# OnOnfre_plug_dev_nao_usar.net
KiCad netlist of a schematic drawn in EAGLE
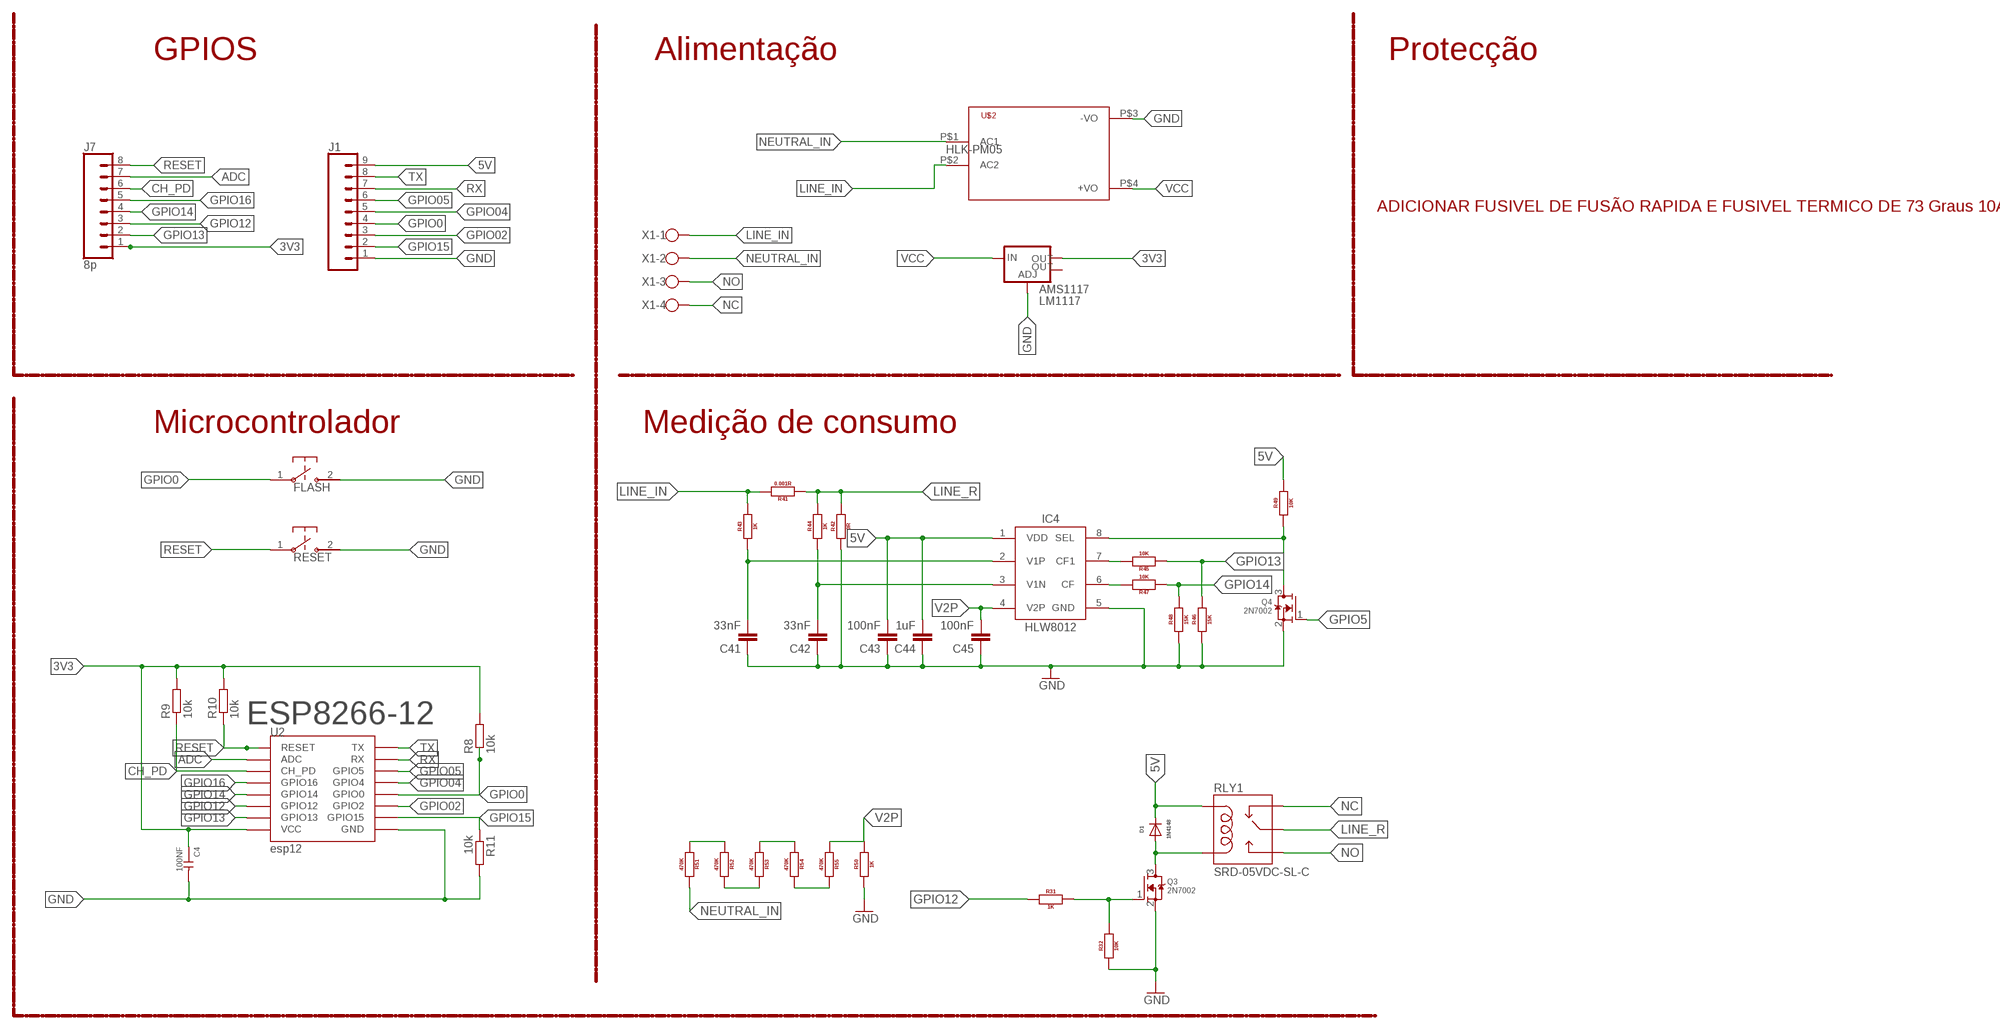
[diagram p0: schematic, sheet 1]

(export (version "E")
  (design (tool "Eeschema 10.0.6"))
  (components
    (comp (ref "AMS1117")
      (value "LM1117")
      (footprint "eagle-import:SOT223")
      (libsource (lib "eagle-import") (part "V_REG_LM1117SOT223"))
    )
    (comp (ref "C4")
      (value "100NF")
      (footprint "eagle-import:C1206")
      (fields (field (name "MPN") "CC1206KKX7RCBB102"))
      (libsource (lib "eagle-import") (part "CERAMIC-1NF-1KV-10%-X7R?(1206)"))
    )
    (comp (ref "C41")
      (value "33nF")
      (footprint "eagle-import:0805")
      (libsource (lib "eagle-import") (part "C-EU0805"))
    )
    (comp (ref "C42")
      (value "33nF")
      (footprint "eagle-import:0805")
      (libsource (lib "eagle-import") (part "C-EU0805"))
    )
    (comp (ref "C43")
      (value "100nF")
      (footprint "eagle-import:0805")
      (libsource (lib "eagle-import") (part "C-EU0805"))
    )
    (comp (ref "C44")
      (value "1uF")
      (footprint "eagle-import:0805")
      (libsource (lib "eagle-import") (part "C-EU0805"))
    )
    (comp (ref "C45")
      (value "100nF")
      (footprint "eagle-import:0805")
      (libsource (lib "eagle-import") (part "C-EU0805"))
    )
    (comp (ref "D1")
      (value "1N4148")
      (footprint "eagle-import:SOD80")
      (libsource (lib "eagle-import") (part "DIODE"))
    )
    (comp (ref "FLASH")
      (value "B3U-1000P-2P-SMD")
      (footprint "eagle-import:B3U-1000P")
      (fields (field (name "MANUFACTURER") "Omron") (field (name "MPN") "B3U-1000P"))
      (libsource (lib "eagle-import") (part "B3U-1000P"))
    )
    (comp (ref "IC4")
      (value "HLW8012")
      (footprint "eagle-import:SOP8")
      (libsource (lib "eagle-import") (part "HLW8012"))
    )
    (comp (ref "J1")
      (value "CONN_09")
      (footprint "eagle-import:1X09")
      (libsource (lib "eagle-import") (part "CONN_09"))
    )
    (comp (ref "J7")
      (value "8p")
      (footprint "eagle-import:1X08")
      (libsource (lib "eagle-import") (part "CONN_08{dblquote}"))
    )
    (comp (ref "Q3")
      (value "2N7002")
      (footprint "eagle-import:SOT23")
      (libsource (lib "eagle-import") (part "MOSFET-NREFLOW"))
    )
    (comp (ref "Q4")
      (value "2N7002")
      (footprint "eagle-import:SOT23")
      (libsource (lib "eagle-import") (part "MOSFET-NREFLOW"))
    )
    (comp (ref "R8")
      (value "10k")
      (footprint "eagle-import:R0603")
      (libsource (lib "eagle-import") (part "R-EU_R0603"))
    )
    (comp (ref "R9")
      (value "10k")
      (footprint "eagle-import:R0603")
      (libsource (lib "eagle-import") (part "R-EU_R0603"))
    )
    (comp (ref "R10")
      (value "10k")
      (footprint "eagle-import:R0603")
      (libsource (lib "eagle-import") (part "R-EU_R0603"))
    )
    (comp (ref "R11")
      (value "10k")
      (footprint "eagle-import:R0603")
      (libsource (lib "eagle-import") (part "R-EU_R0603"))
    )
    (comp (ref "R31")
      (value "1K")
      (footprint "eagle-import:0805")
      (libsource (lib "eagle-import") (part "RESISTOR0805"))
    )
    (comp (ref "R32")
      (value "10K")
      (footprint "eagle-import:0805")
      (libsource (lib "eagle-import") (part "RESISTOR0805"))
    )
    (comp (ref "R41")
      (value "0.001R")
      (footprint "eagle-import:2512")
      (libsource (lib "eagle-import") (part "RESISTOR2512"))
    )
    (comp (ref "R42")
      (value "0R")
      (footprint "eagle-import:1206")
      (libsource (lib "eagle-import") (part "RESISTOR1206"))
    )
    (comp (ref "R43")
      (value "1K")
      (footprint "eagle-import:0805")
      (libsource (lib "eagle-import") (part "RESISTOR0805"))
    )
    (comp (ref "R44")
      (value "1K")
      (footprint "eagle-import:0805")
      (libsource (lib "eagle-import") (part "RESISTOR0805"))
    )
    (comp (ref "R45")
      (value "10K")
      (footprint "eagle-import:0805")
      (libsource (lib "eagle-import") (part "RESISTOR0805"))
    )
    (comp (ref "R46")
      (value "15K")
      (footprint "eagle-import:0805")
      (libsource (lib "eagle-import") (part "RESISTOR0805"))
    )
    (comp (ref "R47")
      (value "10K")
      (footprint "eagle-import:0805")
      (libsource (lib "eagle-import") (part "RESISTOR0805"))
    )
    (comp (ref "R48")
      (value "15K")
      (footprint "eagle-import:0805")
      (libsource (lib "eagle-import") (part "RESISTOR0805"))
    )
    (comp (ref "R49")
      (value "10K")
      (footprint "eagle-import:0805")
      (libsource (lib "eagle-import") (part "RESISTOR0805"))
    )
    (comp (ref "R50")
      (value "1K")
      (footprint "eagle-import:0805")
      (libsource (lib "eagle-import") (part "RESISTOR0805"))
    )
    (comp (ref "R51")
      (value "470K")
      (footprint "eagle-import:0805")
      (libsource (lib "eagle-import") (part "RESISTOR0805"))
    )
    (comp (ref "R52")
      (value "470K")
      (footprint "eagle-import:0805")
      (libsource (lib "eagle-import") (part "RESISTOR0805"))
    )
    (comp (ref "R53")
      (value "470K")
      (footprint "eagle-import:0805")
      (libsource (lib "eagle-import") (part "RESISTOR0805"))
    )
    (comp (ref "R54")
      (value "470K")
      (footprint "eagle-import:0805")
      (libsource (lib "eagle-import") (part "RESISTOR0805"))
    )
    (comp (ref "R55")
      (value "470K")
      (footprint "eagle-import:0805")
      (libsource (lib "eagle-import") (part "RESISTOR0805"))
    )
    (comp (ref "RESET")
      (value "B3U-1000P-2P-SMD")
      (footprint "eagle-import:B3U-1000P")
      (fields (field (name "MANUFACTURER") "Omron") (field (name "MPN") "B3U-1000P"))
      (libsource (lib "eagle-import") (part "B3U-1000P"))
    )
    (comp (ref "RLY1")
      (value "SRD-05VDC-SL-C")
      (footprint "eagle-import:SRD-5VDC-SL-C")
      (libsource (lib "eagle-import") (part "RELAYSONGLE"))
    )
    (comp (ref "U$2")
      (value "HKLPM01")
      (footprint "eagle-import:HKLPM01")
      (libsource (lib "eagle-import") (part "HKLPM01"))
    )
    (comp (ref "U2")
      (value "esp12")
      (footprint "eagle-import:ESP12-SMD")
      (libsource (lib "eagle-import") (part "ESP12SMD"))
    )
    (comp (ref "X1")
      (value "W237-4")
      (footprint "eagle-import:W237-4")
      (libsource (lib "eagle-import") (part "W237-4"))
    )
  )
  (nets
    (net (code "1") (name "3V3") (class "Default")
      (node (ref "AMS1117") (pin "2") (pinfunction "OUT_2") (pintype "output"))
      (node (ref "C4") (pin "1") (pinfunction "1_1") (pintype "passive"))
      (node (ref "J7") (pin "1") (pinfunction "1_1") (pintype "passive"))
      (node (ref "R10") (pin "2") (pinfunction "2_2") (pintype "passive"))
      (node (ref "R8") (pin "2") (pinfunction "2_2") (pintype "passive"))
      (node (ref "R9") (pin "2") (pinfunction "2_2") (pintype "passive"))
      (node (ref "U2") (pin "VCC") (pinfunction "VCC_VCC") (pintype "bidirectional"))
    )
    (net (code "2") (name "5V") (class "Default")
      (node (ref "C43") (pin "2") (pinfunction "2_2") (pintype "passive"))
      (node (ref "C44") (pin "2") (pinfunction "2_2") (pintype "passive"))
      (node (ref "D1") (pin "2") (pinfunction "C_2") (pintype "passive"))
      (node (ref "IC4") (pin "1") (pinfunction "VDD_1") (pintype "power_in"))
      (node (ref "J1") (pin "9") (pinfunction "9_9") (pintype "passive"))
      (node (ref "R49") (pin "2") (pinfunction "2_2") (pintype "passive"))
      (node (ref "RLY1") (pin "COIL1") (pinfunction "COIL1_COIL1") (pintype "bidirectional"))
    )
    (net (code "3") (name "ADC") (class "Default")
      (node (ref "J7") (pin "7") (pinfunction "7_7") (pintype "passive"))
      (node (ref "U2") (pin "ADC") (pinfunction "ADC_ADC") (pintype "bidirectional"))
    )
    (net (code "4") (name "CH_PD") (class "Default")
      (node (ref "J7") (pin "6") (pinfunction "6_6") (pintype "passive"))
      (node (ref "R9") (pin "1") (pinfunction "1_1") (pintype "passive"))
      (node (ref "U2") (pin "CH_PD") (pinfunction "CH_PD_CH_PD") (pintype "bidirectional"))
    )
    (net (code "5") (name "GND") (class "Default")
      (node (ref "AMS1117") (pin "1") (pinfunction "ADJ_1") (pintype "input"))
      (node (ref "C4") (pin "2") (pinfunction "2_2") (pintype "passive"))
      (node (ref "C41") (pin "1") (pinfunction "1_1") (pintype "passive"))
      (node (ref "C42") (pin "1") (pinfunction "1_1") (pintype "passive"))
      (node (ref "C43") (pin "1") (pinfunction "1_1") (pintype "passive"))
      (node (ref "C44") (pin "1") (pinfunction "1_1") (pintype "passive"))
      (node (ref "C45") (pin "1") (pinfunction "1_1") (pintype "passive"))
      (node (ref "FLASH") (pin "2") (pinfunction "P$2_2") (pintype "passive"))
      (node (ref "IC4") (pin "5") (pinfunction "GND_5") (pintype "power_in"))
      (node (ref "J1") (pin "1") (pinfunction "1_1") (pintype "passive"))
      (node (ref "Q3") (pin "2") (pinfunction "S_2") (pintype "bidirectional"))
      (node (ref "Q4") (pin "2") (pinfunction "S_2") (pintype "bidirectional"))
      (node (ref "R11") (pin "2") (pinfunction "2_2") (pintype "passive"))
      (node (ref "R32") (pin "1") (pinfunction "1_1") (pintype "passive"))
      (node (ref "R42") (pin "1") (pinfunction "1_1") (pintype "passive"))
      (node (ref "R46") (pin "1") (pinfunction "1_1") (pintype "passive"))
      (node (ref "R48") (pin "1") (pinfunction "1_1") (pintype "passive"))
      (node (ref "R50") (pin "1") (pinfunction "1_1") (pintype "passive"))
      (node (ref "RESET") (pin "2") (pinfunction "P$2_2") (pintype "passive"))
      (node (ref "U$2") (pin "P$3") (pinfunction "-VO_P$3") (pintype "bidirectional"))
      (node (ref "U2") (pin "GND") (pinfunction "GND_GND") (pintype "bidirectional"))
    )
    (net (code "6") (name "GPIO0") (class "Default")
      (node (ref "FLASH") (pin "1") (pinfunction "P$1_1") (pintype "passive"))
      (node (ref "J1") (pin "4") (pinfunction "4_4") (pintype "passive"))
      (node (ref "R8") (pin "1") (pinfunction "1_1") (pintype "passive"))
      (node (ref "U2") (pin "GPIO0") (pinfunction "GPIO0_GPIO0") (pintype "bidirectional"))
    )
    (net (code "7") (name "GPIO02") (class "Default")
      (node (ref "J1") (pin "3") (pinfunction "3_3") (pintype "passive"))
      (node (ref "U2") (pin "GPIO2") (pinfunction "GPIO2_GPIO2") (pintype "bidirectional"))
    )
    (net (code "8") (name "GPIO04") (class "Default")
      (node (ref "J1") (pin "5") (pinfunction "5_5") (pintype "passive"))
      (node (ref "U2") (pin "GPIO4") (pinfunction "GPIO4_GPIO4") (pintype "bidirectional"))
    )
    (net (code "9") (name "GPIO5") (class "Default")
      (node (ref "Q4") (pin "1") (pinfunction "G_1") (pintype "bidirectional"))
    )
    (net (code "10") (name "GPIO05") (class "Default")
      (node (ref "J1") (pin "6") (pinfunction "6_6") (pintype "passive"))
      (node (ref "U2") (pin "GPIO5") (pinfunction "GPIO5_GPIO5") (pintype "bidirectional"))
    )
    (net (code "11") (name "GPIO12") (class "Default")
      (node (ref "J7") (pin "3") (pinfunction "3_3") (pintype "passive"))
      (node (ref "R31") (pin "1") (pinfunction "1_1") (pintype "passive"))
      (node (ref "U2") (pin "GPIO12") (pinfunction "GPIO12_GPIO12") (pintype "bidirectional"))
    )
    (net (code "12") (name "GPIO13") (class "Default")
      (node (ref "J7") (pin "2") (pinfunction "2_2") (pintype "passive"))
      (node (ref "R45") (pin "1") (pinfunction "1_1") (pintype "passive"))
      (node (ref "R46") (pin "2") (pinfunction "2_2") (pintype "passive"))
      (node (ref "U2") (pin "GPIO13") (pinfunction "GPIO13_GPIO13") (pintype "bidirectional"))
    )
    (net (code "13") (name "GPIO14") (class "Default")
      (node (ref "J7") (pin "4") (pinfunction "4_4") (pintype "passive"))
      (node (ref "R47") (pin "1") (pinfunction "1_1") (pintype "passive"))
      (node (ref "R48") (pin "2") (pinfunction "2_2") (pintype "passive"))
      (node (ref "U2") (pin "GPIO14") (pinfunction "GPIO14_GPIO14") (pintype "bidirectional"))
    )
    (net (code "14") (name "GPIO15") (class "Default")
      (node (ref "J1") (pin "2") (pinfunction "2_2") (pintype "passive"))
      (node (ref "R11") (pin "1") (pinfunction "1_1") (pintype "passive"))
      (node (ref "U2") (pin "GPIO15") (pinfunction "GPIO15_GPIO15") (pintype "bidirectional"))
    )
    (net (code "15") (name "GPIO16") (class "Default")
      (node (ref "J7") (pin "5") (pinfunction "5_5") (pintype "passive"))
      (node (ref "U2") (pin "GPIO16") (pinfunction "GPIO16_GPIO16") (pintype "bidirectional"))
    )
    (net (code "16") (name "LINE_IN") (class "Default")
      (node (ref "R41") (pin "2") (pinfunction "2_2") (pintype "passive"))
      (node (ref "R43") (pin "2") (pinfunction "2_2") (pintype "passive"))
      (node (ref "U$2") (pin "P$2") (pinfunction "AC2_P$2") (pintype "bidirectional"))
      (node (ref "X1") (pin "1") (pinfunction "KL_1") (pintype "passive"))
    )
    (net (code "17") (name "LINE_R") (class "Default")
      (node (ref "R41") (pin "1") (pinfunction "1_1") (pintype "passive"))
      (node (ref "R42") (pin "2") (pinfunction "2_2") (pintype "passive"))
      (node (ref "R44") (pin "2") (pinfunction "2_2") (pintype "passive"))
      (node (ref "RLY1") (pin "COMMON") (pinfunction "MAIN_COMMON") (pintype "bidirectional"))
    )
    (net (code "18") (name "NC") (class "Default")
      (node (ref "RLY1") (pin "CLOSED") (pinfunction "NC_CLOSED") (pintype "bidirectional"))
      (node (ref "X1") (pin "4") (pinfunction "KL_4") (pintype "passive"))
    )
    (net (code "19") (name "NEUTRAL_IN") (class "Default")
      (node (ref "R51") (pin "2") (pinfunction "2_2") (pintype "passive"))
      (node (ref "U$2") (pin "P$1") (pinfunction "AC1_P$1") (pintype "bidirectional"))
      (node (ref "X1") (pin "2") (pinfunction "KL_2") (pintype "passive"))
    )
    (net (code "20") (name "NO") (class "Default")
      (node (ref "RLY1") (pin "OPEN") (pinfunction "NO_OPEN") (pintype "bidirectional"))
      (node (ref "X1") (pin "3") (pinfunction "KL_3") (pintype "passive"))
    )
    (net (code "21") (name "Net-(D1-A)") (class "Default")
      (node (ref "D1") (pin "1") (pinfunction "A_1") (pintype "passive"))
      (node (ref "Q3") (pin "3") (pinfunction "D_3") (pintype "bidirectional"))
      (node (ref "RLY1") (pin "COIL2") (pinfunction "COIL2_COIL2") (pintype "bidirectional"))
    )
    (net (code "22") (name "Net-(IC4-CF)") (class "Default")
      (node (ref "IC4") (pin "6") (pinfunction "CF_6") (pintype "output"))
      (node (ref "R47") (pin "2") (pinfunction "2_2") (pintype "passive"))
    )
    (net (code "23") (name "Net-(IC4-CF1)") (class "Default")
      (node (ref "IC4") (pin "7") (pinfunction "CF1_7") (pintype "output"))
      (node (ref "R45") (pin "2") (pinfunction "2_2") (pintype "passive"))
    )
    (net (code "24") (name "Net-(IC4-SEL)") (class "Default")
      (node (ref "IC4") (pin "8") (pinfunction "SEL_8") (pintype "input"))
      (node (ref "Q4") (pin "3") (pinfunction "D_3") (pintype "bidirectional"))
      (node (ref "R49") (pin "1") (pinfunction "1_1") (pintype "passive"))
    )
    (net (code "25") (name "Net-(IC4-V1N)") (class "Default")
      (node (ref "C42") (pin "2") (pinfunction "2_2") (pintype "passive"))
      (node (ref "IC4") (pin "3") (pinfunction "V1N_3") (pintype "input"))
      (node (ref "R44") (pin "1") (pinfunction "1_1") (pintype "passive"))
    )
    (net (code "26") (name "Net-(IC4-V1P)") (class "Default")
      (node (ref "C41") (pin "2") (pinfunction "2_2") (pintype "passive"))
      (node (ref "IC4") (pin "2") (pinfunction "V1P_2") (pintype "input"))
      (node (ref "R43") (pin "1") (pinfunction "1_1") (pintype "passive"))
    )
    (net (code "27") (name "Net-(Q3-G)") (class "Default")
      (node (ref "Q3") (pin "1") (pinfunction "G_1") (pintype "bidirectional"))
      (node (ref "R31") (pin "2") (pinfunction "2_2") (pintype "passive"))
      (node (ref "R32") (pin "2") (pinfunction "2_2") (pintype "passive"))
    )
    (net (code "28") (name "Net-(R51-Pad1)") (class "Default")
      (node (ref "R51") (pin "1") (pinfunction "1_1") (pintype "passive"))
      (node (ref "R52") (pin "1") (pinfunction "1_1") (pintype "passive"))
    )
    (net (code "29") (name "Net-(R52-Pad2)") (class "Default")
      (node (ref "R52") (pin "2") (pinfunction "2_2") (pintype "passive"))
      (node (ref "R53") (pin "2") (pinfunction "2_2") (pintype "passive"))
    )
    (net (code "30") (name "Net-(R53-Pad1)") (class "Default")
      (node (ref "R53") (pin "1") (pinfunction "1_1") (pintype "passive"))
      (node (ref "R54") (pin "1") (pinfunction "1_1") (pintype "passive"))
    )
    (net (code "31") (name "Net-(R54-Pad2)") (class "Default")
      (node (ref "R54") (pin "2") (pinfunction "2_2") (pintype "passive"))
      (node (ref "R55") (pin "2") (pinfunction "2_2") (pintype "passive"))
    )
    (net (code "32") (name "RESET") (class "Default")
      (node (ref "J7") (pin "8") (pinfunction "8_8") (pintype "passive"))
      (node (ref "R10") (pin "1") (pinfunction "1_1") (pintype "passive"))
      (node (ref "RESET") (pin "1") (pinfunction "P$1_1") (pintype "passive"))
      (node (ref "U2") (pin "RESET") (pinfunction "RESET_RESET") (pintype "bidirectional"))
    )
    (net (code "33") (name "RX") (class "Default")
      (node (ref "J1") (pin "7") (pinfunction "7_7") (pintype "passive"))
      (node (ref "U2") (pin "RXD0") (pinfunction "RX_RXD0") (pintype "bidirectional"))
    )
    (net (code "34") (name "TX") (class "Default")
      (node (ref "J1") (pin "8") (pinfunction "8_8") (pintype "passive"))
      (node (ref "U2") (pin "TXD0") (pinfunction "TX_TXD0") (pintype "bidirectional"))
    )
    (net (code "35") (name "V2P") (class "Default")
      (node (ref "C45") (pin "2") (pinfunction "2_2") (pintype "passive"))
      (node (ref "IC4") (pin "4") (pinfunction "V2P_4") (pintype "input"))
      (node (ref "R50") (pin "2") (pinfunction "2_2") (pintype "passive"))
      (node (ref "R55") (pin "1") (pinfunction "1_1") (pintype "passive"))
    )
    (net (code "36") (name "VCC") (class "Default")
      (node (ref "AMS1117") (pin "3") (pinfunction "IN_3") (pintype "input"))
      (node (ref "U$2") (pin "P$4") (pinfunction "+VO_P$4") (pintype "bidirectional"))
    )
    (net (code "37") (name "unconnected-(AMS1117-OUT-Pad4)") (class "Default")
      (node (ref "AMS1117") (pin "4") (pinfunction "OUT_4") (pintype "output"))
    )
  )
)
